# RF.net
KiCad netlist of a schematic drawn in Altium Designer
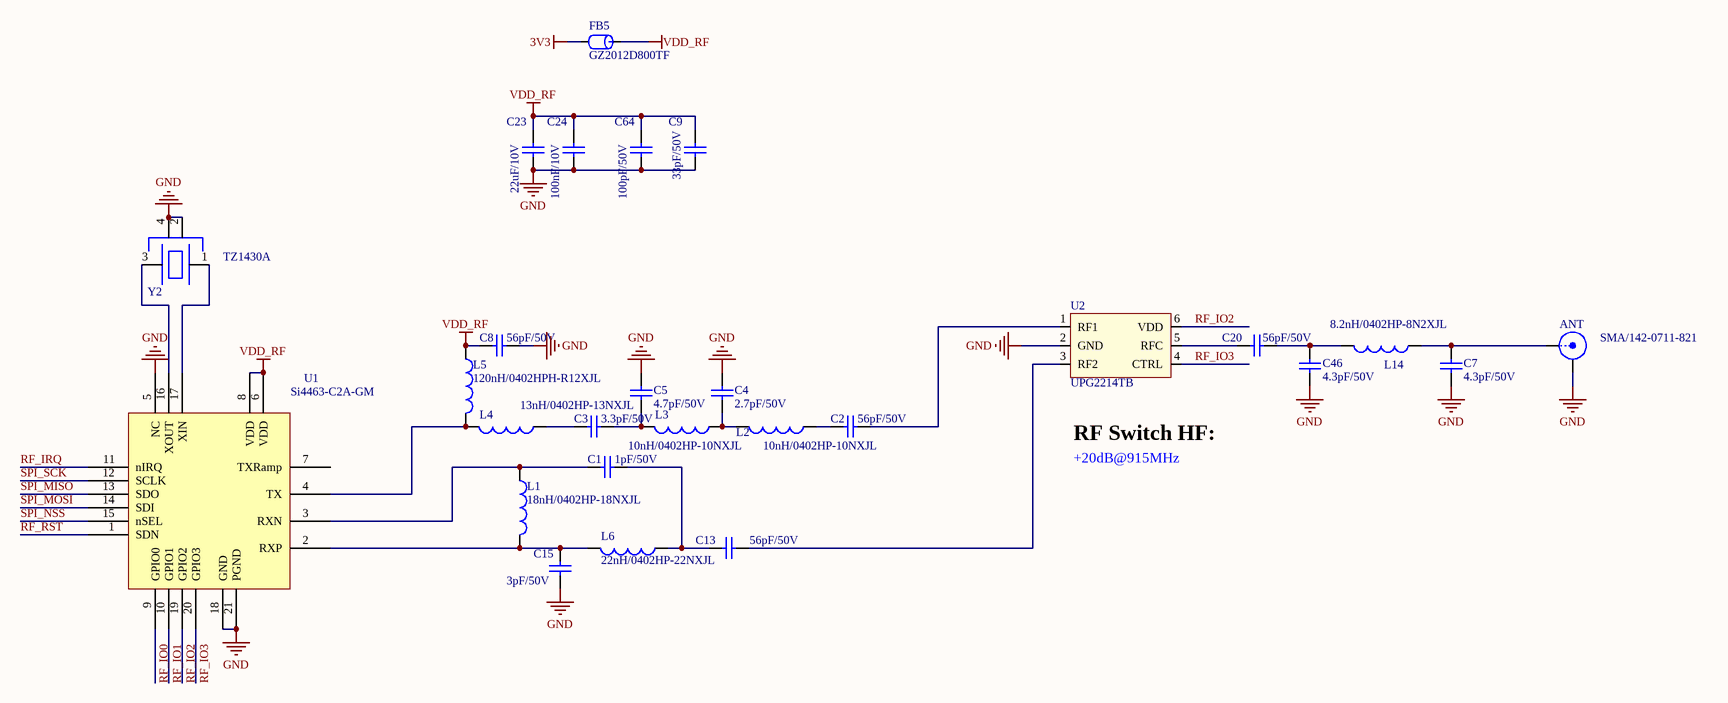
[diagram p0: RF.SchDoc]

(export (version "E")
  (design (tool "Eeschema 10.0.6"))
  (components
    (comp (ref "ANT")
      (value "SMA/142-0711-821")
      (footprint "SMA END LAUNCH JACK RECEPTACLE SHORT")
      (description "SMA Straight Connector")
      (fields (field (name "PUBLISHER") "Altium Limited"))
      (libsource (lib "SX1276_e266v02a") (part "SMA"))
    )
    (comp (ref "C1")
      (value "1pF/50V")
      (footprint "0402C")
      (description "Capacitor SMD")
      (fields (field (name "PUBLISHER") "Altium Limited"))
      (libsource (lib "SX1276_e266v02a") (part "Cap"))
    )
    (comp (ref "C2")
      (value "56pF/50V")
      (footprint "0402C")
      (description "Capacitor SMD")
      (fields (field (name "PUBLISHER") "Altium Limited"))
      (libsource (lib "SX1276_e266v02a") (part "Cap"))
    )
    (comp (ref "C3")
      (value "3.3pF/50V")
      (footprint "0402C")
      (description "Capacitor SMD")
      (fields (field (name "PUBLISHER") "Altium Limited"))
      (libsource (lib "SX1276_e266v02a") (part "Cap"))
    )
    (comp (ref "C4")
      (value "2.7pF/50V")
      (footprint "0402C")
      (description "Capacitor SMD")
      (fields (field (name "PUBLISHER") "Altium Limited"))
      (libsource (lib "SX1276_e266v02a") (part "Cap"))
    )
    (comp (ref "C5")
      (value "4.7pF/50V")
      (footprint "0402C")
      (description "Capacitor SMD")
      (fields (field (name "PUBLISHER") "Altium Limited"))
      (libsource (lib "SX1276_e266v02a") (part "Cap"))
    )
    (comp (ref "C7")
      (value "4.3pF/50V")
      (footprint "0402C")
      (description "Capacitor SMD")
      (fields (field (name "PUBLISHER") "Altium Limited"))
      (libsource (lib "SX1276_e266v02a") (part "Cap"))
    )
    (comp (ref "C8")
      (value "56pF/50V")
      (footprint "0402C")
      (description "Capacitor SMD")
      (fields (field (name "PUBLISHER") "Altium Limited"))
      (libsource (lib "SX1276_e266v02a") (part "Cap"))
    )
    (comp (ref "C9")
      (value "33pF/50V")
      (footprint "0603C")
      (description "Capacitor (Semiconductor SIM Model)")
      (fields (field (name "PUBLISHER") "Altium Limited"))
      (libsource (lib "SX1276_e266v02a") (part "Cap Semi"))
    )
    (comp (ref "C13")
      (value "56pF/50V")
      (footprint "0402C")
      (description "Capacitor SMD")
      (fields (field (name "PUBLISHER") "Altium Limited"))
      (libsource (lib "SX1276_e266v02a") (part "Cap"))
    )
    (comp (ref "C15")
      (value "3pF/50V")
      (footprint "0402C")
      (description "Capacitor SMD")
      (fields (field (name "PUBLISHER") "Altium Limited"))
      (libsource (lib "SX1276_e266v02a") (part "Cap"))
    )
    (comp (ref "C20")
      (value "56pF/50V")
      (footprint "0402C")
      (description "Capacitor SMD")
      (fields (field (name "PUBLISHER") "Altium Limited"))
      (libsource (lib "SX1276_e266v02a") (part "Cap"))
    )
    (comp (ref "C23")
      (value "22uF/10V")
      (footprint "0805C")
      (description "Capacitor (Semiconductor SIM Model)")
      (fields (field (name "PUBLISHER") "Altium Limited"))
      (libsource (lib "SX1276_e266v02a") (part "Cap Semi"))
    )
    (comp (ref "C24")
      (value "100nF/10V")
      (footprint "0603C")
      (description "Capacitor (Semiconductor SIM Model)")
      (fields (field (name "PUBLISHER") "Altium Limited"))
      (libsource (lib "SX1276_e266v02a") (part "Cap Semi"))
    )
    (comp (ref "C46")
      (value "4.3pF/50V")
      (footprint "0402C")
      (description "Capacitor SMD")
      (fields (field (name "PUBLISHER") "Altium Limited"))
      (libsource (lib "SX1276_e266v02a") (part "Cap"))
    )
    (comp (ref "C64")
      (value "100pF/50V")
      (footprint "0603C")
      (description "Capacitor (Semiconductor SIM Model)")
      (fields (field (name "PUBLISHER") "Altium Limited"))
      (libsource (lib "SX1276_e266v02a") (part "Cap Semi"))
    )
    (comp (ref "FB5")
      (value "GZ2012D800TF")
      (footprint "0805CZ")
      (libsource (lib "Schlib_20110825") (part "FB"))
    )
    (comp (ref "L1")
      (value "18nH/0402HP-18NXJL")
      (footprint "0402R")
      (description "Inductor SMD")
      (fields (field (name "PUBLISHER") "Altium Limited"))
      (libsource (lib "SX1276_e266v02a") (part "Inductor"))
    )
    (comp (ref "L2")
      (value "10nH/0402HP-10NXJL")
      (footprint "0402R")
      (description "Inductor SMD")
      (fields (field (name "PUBLISHER") "Altium Limited"))
      (libsource (lib "SX1276_e266v02a") (part "Inductor"))
    )
    (comp (ref "L3")
      (value "10nH/0402HP-10NXJL")
      (footprint "0402R")
      (description "Inductor SMD")
      (fields (field (name "PUBLISHER") "Altium Limited"))
      (libsource (lib "SX1276_e266v02a") (part "Inductor"))
    )
    (comp (ref "L4")
      (value "13nH/0402HP-13NXJL")
      (footprint "0402R")
      (description "Inductor SMD")
      (fields (field (name "PUBLISHER") "Altium Limited"))
      (libsource (lib "SX1276_e266v02a") (part "Inductor"))
    )
    (comp (ref "L5")
      (value "120nH/0402HPH-R12XJL")
      (footprint "0402R")
      (description "Inductor SMD")
      (fields (field (name "PUBLISHER") "Altium Limited"))
      (libsource (lib "SX1276_e266v02a") (part "Inductor"))
    )
    (comp (ref "L6")
      (value "22nH/0402HP-22NXJL")
      (footprint "0402R")
      (description "Inductor SMD")
      (fields (field (name "PUBLISHER") "Altium Limited"))
      (libsource (lib "SX1276_e266v02a") (part "Inductor"))
    )
    (comp (ref "L14")
      (value "8.2nH/0402HP-8N2XJL")
      (footprint "0402R")
      (description "Inductor SMD")
      (fields (field (name "PUBLISHER") "Altium Limited"))
      (libsource (lib "SX1276_e266v02a") (part "Inductor"))
    )
    (comp (ref "U1")
      (value "Si4463-C2A-GM")
      (footprint "Pcblib_20110825:QFN50P400X400X80-20N")
      (libsource (lib "stm32") (part "Si4463"))
    )
    (comp (ref "U2")
      (value "UPG2214TB")
      (footprint "SC70-6")
      (description "PE4259 Peregrine RF Switch")
      (libsource (lib "SX1276_e266v02a") (part "PE4259 RF Switch"))
    )
    (comp (ref "Y2")
      (value "TZ1430A")
      (footprint "OSCILLATOR-2.5X2.0")
      (libsource (lib "Myself_1") (part "XTAL3"))
    )
  )
  (nets
    (net (code "1") (name "/RF_IO0") (class "Default")
      (node (ref "U1") (pin "9") (pinfunction "GPIO0_9") (pintype "passive"))
    )
    (net (code "2") (name "/RF_IO1") (class "Default")
      (node (ref "U1") (pin "10") (pinfunction "GPIO1_10") (pintype "passive"))
    )
    (net (code "3") (name "/RF_IO2") (class "Default")
      (node (ref "U1") (pin "19") (pinfunction "GPIO2_19") (pintype "passive"))
      (node (ref "U2") (pin "6") (pinfunction "VDD_6") (pintype "passive"))
    )
    (net (code "4") (name "/RF_IO3") (class "Default")
      (node (ref "U1") (pin "20") (pinfunction "GPIO3_20") (pintype "passive"))
      (node (ref "U2") (pin "4") (pinfunction "CTRL_4") (pintype "passive"))
    )
    (net (code "5") (name "/RF_IRQ") (class "Default")
      (node (ref "U1") (pin "11") (pinfunction "nIRQ_11") (pintype "passive"))
    )
    (net (code "6") (name "/RF_RST") (class "Default")
      (node (ref "U1") (pin "1") (pinfunction "SDN_1") (pintype "passive"))
    )
    (net (code "7") (name "/SPI_MISO") (class "Default")
      (node (ref "U1") (pin "13") (pinfunction "SDO_13") (pintype "passive"))
    )
    (net (code "8") (name "/SPI_MOSI") (class "Default")
      (node (ref "U1") (pin "14") (pinfunction "SDI_14") (pintype "passive"))
    )
    (net (code "9") (name "/SPI_NSS") (class "Default")
      (node (ref "U1") (pin "15") (pinfunction "nSEL_15") (pintype "passive"))
    )
    (net (code "10") (name "/SPI_SCK") (class "Default")
      (node (ref "U1") (pin "12") (pinfunction "SCLK_12") (pintype "passive"))
    )
    (net (code "11") (name "3V3") (class "Default") (node (ref "FB5") (pin "2") (pintype "passive")))
    (net (code "12") (name "GND") (class "Default")
      (node (ref "ANT") (pin "2") (pinfunction "GND_2") (pintype "passive"))
      (node (ref "C15") (pin "1") (pinfunction "1_1") (pintype "passive"))
      (node (ref "C23") (pin "1") (pinfunction "1_1") (pintype "passive"))
      (node (ref "C24") (pin "1") (pinfunction "1_1") (pintype "passive"))
      (node (ref "C4") (pin "2") (pinfunction "2_2") (pintype "passive"))
      (node (ref "C46") (pin "1") (pinfunction "1_1") (pintype "passive"))
      (node (ref "C5") (pin "2") (pinfunction "2_2") (pintype "passive"))
      (node (ref "C64") (pin "1") (pinfunction "1_1") (pintype "passive"))
      (node (ref "C7") (pin "1") (pinfunction "1_1") (pintype "passive"))
      (node (ref "C8") (pin "2") (pinfunction "2_2") (pintype "passive"))
      (node (ref "C9") (pin "1") (pinfunction "1_1") (pintype "passive"))
      (node (ref "U1") (pin "18") (pinfunction "GND_18") (pintype "passive"))
      (node (ref "U1") (pin "21") (pinfunction "PGND_21") (pintype "passive"))
      (node (ref "U1") (pin "5") (pinfunction "NC_5") (pintype "passive"))
      (node (ref "U2") (pin "2") (pinfunction "GND_2") (pintype "passive"))
      (node (ref "Y2") (pin "2") (pinfunction "GND_2") (pintype "passive"))
      (node (ref "Y2") (pin "4") (pinfunction "GND_4") (pintype "passive"))
    )
    (net (code "13") (name "Net-(ANT-Signal)") (class "Default")
      (node (ref "ANT") (pin "1") (pinfunction "Signal_1") (pintype "passive"))
      (node (ref "C7") (pin "2") (pinfunction "2_2") (pintype "passive"))
      (node (ref "L14") (pin "1") (pinfunction "1_1") (pintype "passive"))
    )
    (net (code "14") (name "Net-(C1-Pad2)") (class "Default")
      (node (ref "C1") (pin "2") (pinfunction "2_2") (pintype "passive"))
      (node (ref "C13") (pin "1") (pinfunction "1_1") (pintype "passive"))
      (node (ref "L6") (pin "1") (pinfunction "1_1") (pintype "passive"))
    )
    (net (code "15") (name "Net-(C2-Pad2)") (class "Default")
      (node (ref "C2") (pin "2") (pinfunction "2_2") (pintype "passive"))
      (node (ref "L2") (pin "1") (pinfunction "1_1") (pintype "passive"))
    )
    (net (code "16") (name "Net-(C3-Pad1)") (class "Default")
      (node (ref "C3") (pin "1") (pinfunction "1_1") (pintype "passive"))
      (node (ref "L4") (pin "1") (pinfunction "1_1") (pintype "passive"))
    )
    (net (code "17") (name "Net-(C3-Pad2)") (class "Default")
      (node (ref "C3") (pin "2") (pinfunction "2_2") (pintype "passive"))
      (node (ref "C5") (pin "1") (pinfunction "1_1") (pintype "passive"))
      (node (ref "L3") (pin "2") (pinfunction "2_2") (pintype "passive"))
    )
    (net (code "18") (name "Net-(C4-Pad1)") (class "Default")
      (node (ref "C4") (pin "1") (pinfunction "1_1") (pintype "passive"))
      (node (ref "L2") (pin "2") (pinfunction "2_2") (pintype "passive"))
      (node (ref "L3") (pin "1") (pinfunction "1_1") (pintype "passive"))
    )
    (net (code "19") (name "Net-(C20-Pad1)") (class "Default")
      (node (ref "C20") (pin "1") (pinfunction "1_1") (pintype "passive"))
      (node (ref "C46") (pin "2") (pinfunction "2_2") (pintype "passive"))
      (node (ref "L14") (pin "2") (pinfunction "2_2") (pintype "passive"))
    )
    (net (code "20") (name "Net-(U1-RXN)") (class "Default")
      (node (ref "C1") (pin "1") (pinfunction "1_1") (pintype "passive"))
      (node (ref "L1") (pin "1") (pinfunction "1_1") (pintype "passive"))
      (node (ref "U1") (pin "3") (pinfunction "RXN_3") (pintype "passive"))
    )
    (net (code "21") (name "Net-(U1-RXP)") (class "Default")
      (node (ref "C15") (pin "2") (pinfunction "2_2") (pintype "passive"))
      (node (ref "L1") (pin "2") (pinfunction "2_2") (pintype "passive"))
      (node (ref "L6") (pin "2") (pinfunction "2_2") (pintype "passive"))
      (node (ref "U1") (pin "2") (pinfunction "RXP_2") (pintype "passive"))
    )
    (net (code "22") (name "Net-(U1-TX)") (class "Default")
      (node (ref "L4") (pin "2") (pinfunction "2_2") (pintype "passive"))
      (node (ref "L5") (pin "2") (pinfunction "2_2") (pintype "passive"))
      (node (ref "U1") (pin "4") (pinfunction "TX_4") (pintype "passive"))
    )
    (net (code "23") (name "Net-(U1-XIN)") (class "Default")
      (node (ref "U1") (pin "17") (pinfunction "XIN_17") (pintype "passive"))
      (node (ref "Y2") (pin "1") (pinfunction "1_1") (pintype "passive"))
    )
    (net (code "24") (name "Net-(U1-XOUT)") (class "Default")
      (node (ref "U1") (pin "16") (pinfunction "XOUT_16") (pintype "passive"))
      (node (ref "Y2") (pin "3") (pinfunction "3_3") (pintype "passive"))
    )
    (net (code "25") (name "Net-(U2-RF1)") (class "Default")
      (node (ref "C2") (pin "1") (pinfunction "1_1") (pintype "passive"))
      (node (ref "U2") (pin "1") (pinfunction "RF1_1") (pintype "passive"))
    )
    (net (code "26") (name "Net-(U2-RF2)") (class "Default")
      (node (ref "C13") (pin "2") (pinfunction "2_2") (pintype "passive"))
      (node (ref "U2") (pin "3") (pinfunction "RF2_3") (pintype "passive"))
    )
    (net (code "27") (name "Net-(U2-RFC)") (class "Default")
      (node (ref "C20") (pin "2") (pinfunction "2_2") (pintype "passive"))
      (node (ref "U2") (pin "5") (pinfunction "RFC_5") (pintype "passive"))
    )
    (net (code "28") (name "VDD_RF") (class "Default")
      (node (ref "C23") (pin "2") (pinfunction "2_2") (pintype "passive"))
      (node (ref "C24") (pin "2") (pinfunction "2_2") (pintype "passive"))
      (node (ref "C64") (pin "2") (pinfunction "2_2") (pintype "passive"))
      (node (ref "C8") (pin "1") (pinfunction "1_1") (pintype "passive"))
      (node (ref "C9") (pin "2") (pinfunction "2_2") (pintype "passive"))
      (node (ref "FB5") (pin "1") (pintype "passive"))
      (node (ref "L5") (pin "1") (pinfunction "1_1") (pintype "passive"))
      (node (ref "U1") (pin "6") (pinfunction "VDD_6") (pintype "passive"))
      (node (ref "U1") (pin "8") (pinfunction "VDD_8") (pintype "passive"))
    )
    (net (code "29") (name "unconnected-(U1-TXRamp-Pad7)") (class "Default")
      (node (ref "U1") (pin "7") (pinfunction "TXRamp_7") (pintype "passive"))
    )
  )
)
